# EMMC.net
KiCad netlist of a schematic drawn in Altium Designer
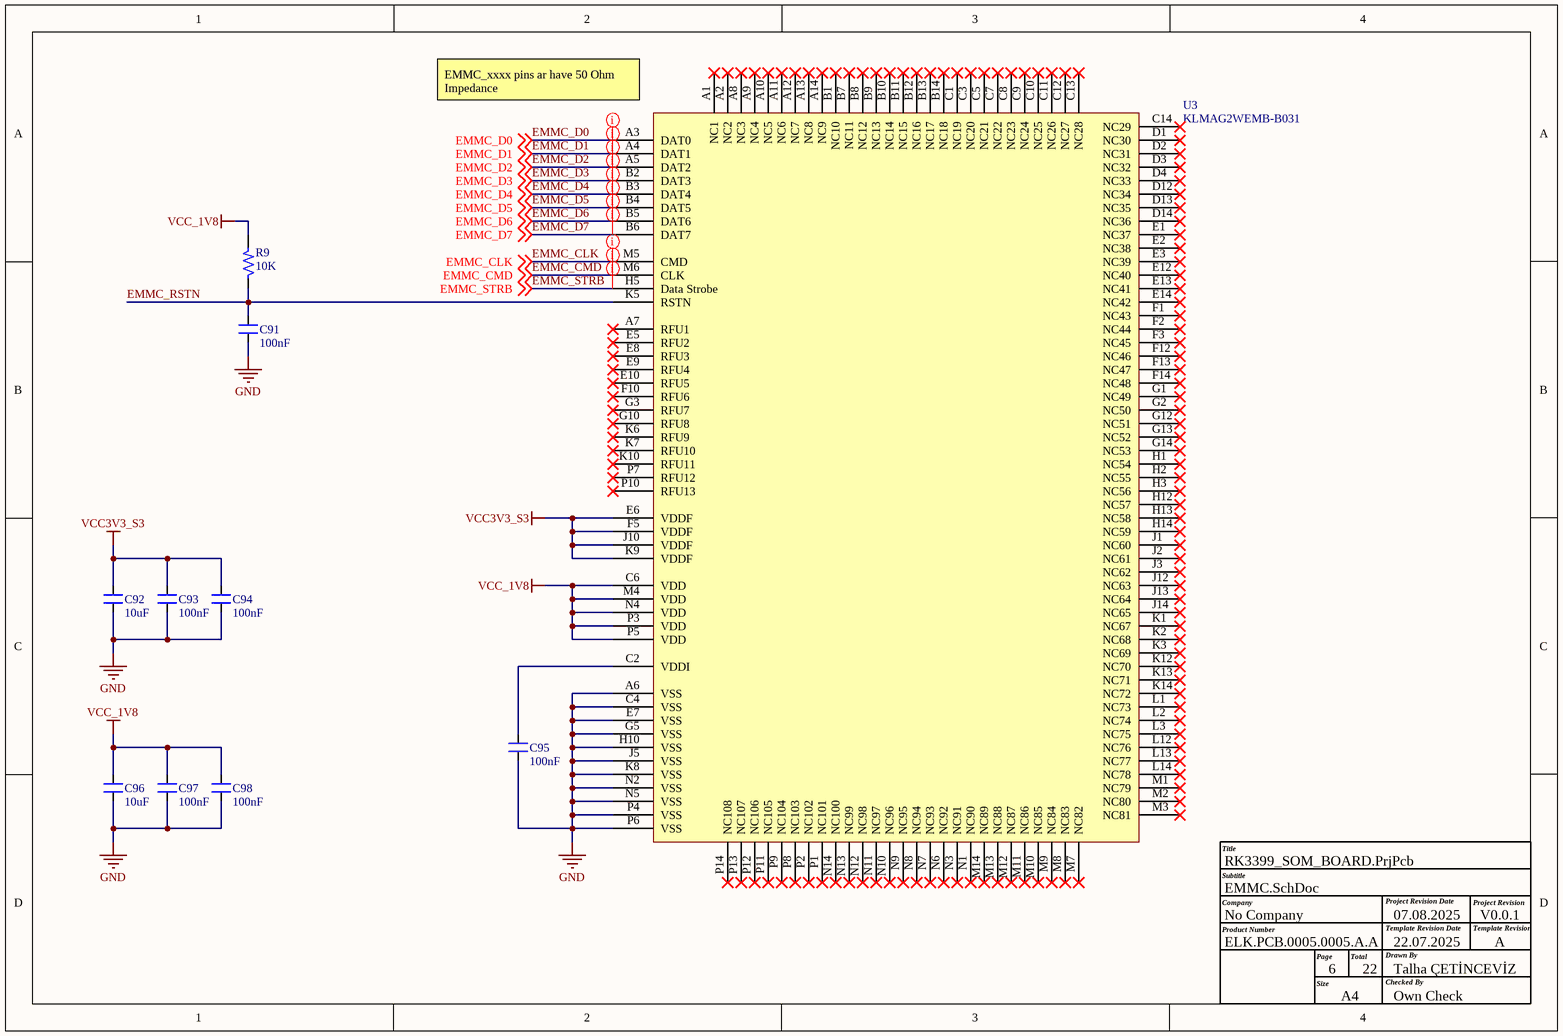
[diagram p0: EMMC.SchDoc]

(export (version "E")
  (design (tool "Eeschema 10.0.6"))
  (components
    (comp (ref "C91")
      (value "100nF")
      (footprint "CAP_0201")
      (description "0.1µF ±10% 25V Ceramic Capacitor X5R 0201 (0603 Metric)")
      (fields
        (field (name "MANUFACTURER") "TDK Corporation")
        (field (name "MANUFACTURER PART NUMBER") "C0603X5R1E104K030BB")
      )
      (libsource (lib "EsteemPCB_SOM_Course_intlib") (part "CAP_100nF-25V-10%-0201"))
    )
    (comp (ref "C92")
      (value "10uF")
      (footprint "CAP_0603")
      (description "10µF ±10% 10V Ceramic Capacitor X5R 0603 (1608 Metric)")
      (fields
        (field (name "MANUFACTURER PART NUMBER") "GRM188R61A106KE69J")
        (field (name "MANUFACTURER") "Murata Electronics")
      )
      (libsource (lib "EsteemPCB_SOM_Course_intlib") (part "CAP_10uF-10V-10%-0603"))
    )
    (comp (ref "C93")
      (value "100nF")
      (footprint "CAP_0201")
      (description "0.1µF ±10% 25V Ceramic Capacitor X5R 0201 (0603 Metric)")
      (fields
        (field (name "MANUFACTURER") "TDK Corporation")
        (field (name "MANUFACTURER PART NUMBER") "C0603X5R1E104K030BB")
      )
      (libsource (lib "EsteemPCB_SOM_Course_intlib") (part "CAP_100nF-25V-10%-0201"))
    )
    (comp (ref "C94")
      (value "100nF")
      (footprint "CAP_0201")
      (description "0.1µF ±10% 25V Ceramic Capacitor X5R 0201 (0603 Metric)")
      (fields
        (field (name "MANUFACTURER") "TDK Corporation")
        (field (name "MANUFACTURER PART NUMBER") "C0603X5R1E104K030BB")
      )
      (libsource (lib "EsteemPCB_SOM_Course_intlib") (part "CAP_100nF-25V-10%-0201"))
    )
    (comp (ref "C95")
      (value "100nF")
      (footprint "CAP_0201")
      (description "0.1µF ±10% 25V Ceramic Capacitor X5R 0201 (0603 Metric)")
      (fields
        (field (name "MANUFACTURER") "TDK Corporation")
        (field (name "MANUFACTURER PART NUMBER") "C0603X5R1E104K030BB")
      )
      (libsource (lib "EsteemPCB_SOM_Course_intlib") (part "CAP_100nF-25V-10%-0201"))
    )
    (comp (ref "C96")
      (value "10uF")
      (footprint "CAP_0603")
      (description "10µF ±10% 10V Ceramic Capacitor X5R 0603 (1608 Metric)")
      (fields
        (field (name "MANUFACTURER PART NUMBER") "GRM188R61A106KE69J")
        (field (name "MANUFACTURER") "Murata Electronics")
      )
      (libsource (lib "EsteemPCB_SOM_Course_intlib") (part "CAP_10uF-10V-10%-0603"))
    )
    (comp (ref "C97")
      (value "100nF")
      (footprint "CAP_0201")
      (description "0.1µF ±10% 25V Ceramic Capacitor X5R 0201 (0603 Metric)")
      (fields
        (field (name "MANUFACTURER") "TDK Corporation")
        (field (name "MANUFACTURER PART NUMBER") "C0603X5R1E104K030BB")
      )
      (libsource (lib "EsteemPCB_SOM_Course_intlib") (part "CAP_100nF-25V-10%-0201"))
    )
    (comp (ref "C98")
      (value "100nF")
      (footprint "CAP_0201")
      (description "0.1µF ±10% 25V Ceramic Capacitor X5R 0201 (0603 Metric)")
      (fields
        (field (name "MANUFACTURER") "TDK Corporation")
        (field (name "MANUFACTURER PART NUMBER") "C0603X5R1E104K030BB")
      )
      (libsource (lib "EsteemPCB_SOM_Course_intlib") (part "CAP_100nF-25V-10%-0201"))
    )
    (comp (ref "R9")
      (value "10K")
      (footprint "RES_0201")
      (description "10 kOhms ±1% 0.05W, 1/20W Chip Resistor 0201 (0603 Metric) Thick Film")
      (fields
        (field (name "MANUFACTURER") "Stackpole Electronics Inc")
        (field (name "MANUFACTURER PART NUMBER") "RMCF0201FT10K0")
      )
      (libsource (lib "EsteemPCB_SOM_Course_intlib") (part "RES_10K-0.05W-1%-0201"))
    )
    (comp (ref "U3")
      (value "KLMAG2WEMB-B031")
      (footprint "BGA153C50P14X14_1150X1300X70")
      (description "16GB NAND Flash Memory")
      (fields (field (name "MANUFACTURER") "Samsung Electronics"))
      (libsource (lib "EsteemPCB_SOM_Course_intlib") (part "IC_KLMAG2WEMB-B031"))
    )
  )
  (nets
    (net (code "1") (name "/EMMC_RSTN") (class "Default")
      (node (ref "C91") (pin "2") (pinfunction "2_2") (pintype "passive"))
      (node (ref "R9") (pin "1") (pinfunction "1_1") (pintype "passive"))
      (node (ref "U3") (pin "K5") (pinfunction "RSTN_K5") (pintype "passive"))
    )
    (net (code "2") (name "EMMC_CLK") (class "Default")
      (node (ref "U3") (pin "M5") (pinfunction "CMD_M5") (pintype "passive"))
    )
    (net (code "3") (name "EMMC_CMD") (class "Default")
      (node (ref "U3") (pin "M6") (pinfunction "CLK_M6") (pintype "passive"))
    )
    (net (code "4") (name "EMMC_D0") (class "Default")
      (node (ref "U3") (pin "A3") (pinfunction "DAT0_A3") (pintype "passive"))
    )
    (net (code "5") (name "EMMC_D1") (class "Default")
      (node (ref "U3") (pin "A4") (pinfunction "DAT1_A4") (pintype "passive"))
    )
    (net (code "6") (name "EMMC_D2") (class "Default")
      (node (ref "U3") (pin "A5") (pinfunction "DAT2_A5") (pintype "passive"))
    )
    (net (code "7") (name "EMMC_D3") (class "Default")
      (node (ref "U3") (pin "B2") (pinfunction "DAT3_B2") (pintype "passive"))
    )
    (net (code "8") (name "EMMC_D4") (class "Default")
      (node (ref "U3") (pin "B3") (pinfunction "DAT4_B3") (pintype "passive"))
    )
    (net (code "9") (name "EMMC_D5") (class "Default")
      (node (ref "U3") (pin "B4") (pinfunction "DAT5_B4") (pintype "passive"))
    )
    (net (code "10") (name "EMMC_D6") (class "Default")
      (node (ref "U3") (pin "B5") (pinfunction "DAT6_B5") (pintype "passive"))
    )
    (net (code "11") (name "EMMC_D7") (class "Default")
      (node (ref "U3") (pin "B6") (pinfunction "DAT7_B6") (pintype "passive"))
    )
    (net (code "12") (name "EMMC_STRB") (class "Default")
      (node (ref "U3") (pin "H5") (pinfunction "Data_Strobe_H5") (pintype "passive"))
    )
    (net (code "13") (name "GND") (class "Default")
      (node (ref "C91") (pin "1") (pinfunction "1_1") (pintype "passive"))
      (node (ref "C92") (pin "1") (pinfunction "1_1") (pintype "passive"))
      (node (ref "C93") (pin "1") (pinfunction "1_1") (pintype "passive"))
      (node (ref "C94") (pin "1") (pinfunction "1_1") (pintype "passive"))
      (node (ref "C95") (pin "2") (pinfunction "2_2") (pintype "passive"))
      (node (ref "C96") (pin "1") (pinfunction "1_1") (pintype "passive"))
      (node (ref "C97") (pin "1") (pinfunction "1_1") (pintype "passive"))
      (node (ref "C98") (pin "1") (pinfunction "1_1") (pintype "passive"))
      (node (ref "U3") (pin "A6") (pinfunction "VSS_A6") (pintype "passive"))
      (node (ref "U3") (pin "C4") (pinfunction "VSS_C4") (pintype "passive"))
      (node (ref "U3") (pin "E7") (pinfunction "VSS_E7") (pintype "passive"))
      (node (ref "U3") (pin "G5") (pinfunction "VSS_G5") (pintype "passive"))
      (node (ref "U3") (pin "H10") (pinfunction "VSS_H10") (pintype "passive"))
      (node (ref "U3") (pin "J5") (pinfunction "VSS_J5") (pintype "passive"))
      (node (ref "U3") (pin "K8") (pinfunction "VSS_K8") (pintype "passive"))
      (node (ref "U3") (pin "N2") (pinfunction "VSS_N2") (pintype "passive"))
      (node (ref "U3") (pin "N5") (pinfunction "VSS_N5") (pintype "passive"))
      (node (ref "U3") (pin "P4") (pinfunction "VSS_P4") (pintype "passive"))
      (node (ref "U3") (pin "P6") (pinfunction "VSS_P6") (pintype "passive"))
    )
    (net (code "14") (name "Net-(U3-VDDI)") (class "Default")
      (node (ref "C95") (pin "1") (pinfunction "1_1") (pintype "passive"))
      (node (ref "U3") (pin "C2") (pinfunction "VDDI_C2") (pintype "passive"))
    )
    (net (code "15") (name "VCC3V3_S3") (class "Default")
      (node (ref "C92") (pin "2") (pinfunction "2_2") (pintype "passive"))
      (node (ref "C93") (pin "2") (pinfunction "2_2") (pintype "passive"))
      (node (ref "C94") (pin "2") (pinfunction "2_2") (pintype "passive"))
      (node (ref "U3") (pin "E6") (pinfunction "VDDF_E6") (pintype "passive"))
      (node (ref "U3") (pin "F5") (pinfunction "VDDF_F5") (pintype "passive"))
      (node (ref "U3") (pin "J10") (pinfunction "VDDF_J10") (pintype "passive"))
      (node (ref "U3") (pin "K9") (pinfunction "VDDF_K9") (pintype "passive"))
    )
    (net (code "16") (name "VCC_1V8") (class "Default")
      (node (ref "C96") (pin "2") (pinfunction "2_2") (pintype "passive"))
      (node (ref "C97") (pin "2") (pinfunction "2_2") (pintype "passive"))
      (node (ref "C98") (pin "2") (pinfunction "2_2") (pintype "passive"))
      (node (ref "R9") (pin "2") (pinfunction "2_2") (pintype "passive"))
      (node (ref "U3") (pin "C6") (pinfunction "VDD_C6") (pintype "passive"))
      (node (ref "U3") (pin "M4") (pinfunction "VDD_M4") (pintype "passive"))
      (node (ref "U3") (pin "N4") (pinfunction "VDD_N4") (pintype "passive"))
      (node (ref "U3") (pin "P3") (pinfunction "VDD_P3") (pintype "passive"))
      (node (ref "U3") (pin "P5") (pinfunction "VDD_P5") (pintype "passive"))
    )
    (net (code "17") (name "unconnected-(U3-NC1-PadA1)") (class "Default")
      (node (ref "U3") (pin "A1") (pinfunction "NC1_A1") (pintype "passive+no_connect"))
    )
    (net (code "18") (name "unconnected-(U3-NC2-PadA2)") (class "Default")
      (node (ref "U3") (pin "A2") (pinfunction "NC2_A2") (pintype "passive+no_connect"))
    )
    (net (code "19") (name "unconnected-(U3-NC3-PadA8)") (class "Default")
      (node (ref "U3") (pin "A8") (pinfunction "NC3_A8") (pintype "passive+no_connect"))
    )
    (net (code "20") (name "unconnected-(U3-NC4-PadA9)") (class "Default")
      (node (ref "U3") (pin "A9") (pinfunction "NC4_A9") (pintype "passive+no_connect"))
    )
    (net (code "21") (name "unconnected-(U3-NC5-PadA10)") (class "Default")
      (node (ref "U3") (pin "A10") (pinfunction "NC5_A10") (pintype "passive+no_connect"))
    )
    (net (code "22") (name "unconnected-(U3-NC6-PadA11)") (class "Default")
      (node (ref "U3") (pin "A11") (pinfunction "NC6_A11") (pintype "passive+no_connect"))
    )
    (net (code "23") (name "unconnected-(U3-NC7-PadA12)") (class "Default")
      (node (ref "U3") (pin "A12") (pinfunction "NC7_A12") (pintype "passive+no_connect"))
    )
    (net (code "24") (name "unconnected-(U3-NC8-PadA13)") (class "Default")
      (node (ref "U3") (pin "A13") (pinfunction "NC8_A13") (pintype "passive+no_connect"))
    )
    (net (code "25") (name "unconnected-(U3-NC9-PadA14)") (class "Default")
      (node (ref "U3") (pin "A14") (pinfunction "NC9_A14") (pintype "passive+no_connect"))
    )
    (net (code "26") (name "unconnected-(U3-NC10-PadB1)") (class "Default")
      (node (ref "U3") (pin "B1") (pinfunction "NC10_B1") (pintype "passive+no_connect"))
    )
    (net (code "27") (name "unconnected-(U3-NC11-PadB7)") (class "Default")
      (node (ref "U3") (pin "B7") (pinfunction "NC11_B7") (pintype "passive+no_connect"))
    )
    (net (code "28") (name "unconnected-(U3-NC12-PadB8)") (class "Default")
      (node (ref "U3") (pin "B8") (pinfunction "NC12_B8") (pintype "passive+no_connect"))
    )
    (net (code "29") (name "unconnected-(U3-NC13-PadB9)") (class "Default")
      (node (ref "U3") (pin "B9") (pinfunction "NC13_B9") (pintype "passive+no_connect"))
    )
    (net (code "30") (name "unconnected-(U3-NC14-PadB10)") (class "Default")
      (node (ref "U3") (pin "B10") (pinfunction "NC14_B10") (pintype "passive+no_connect"))
    )
    (net (code "31") (name "unconnected-(U3-NC15-PadB11)") (class "Default")
      (node (ref "U3") (pin "B11") (pinfunction "NC15_B11") (pintype "passive+no_connect"))
    )
    (net (code "32") (name "unconnected-(U3-NC16-PadB12)") (class "Default")
      (node (ref "U3") (pin "B12") (pinfunction "NC16_B12") (pintype "passive+no_connect"))
    )
    (net (code "33") (name "unconnected-(U3-NC17-PadB13)") (class "Default")
      (node (ref "U3") (pin "B13") (pinfunction "NC17_B13") (pintype "passive+no_connect"))
    )
    (net (code "34") (name "unconnected-(U3-NC18-PadB14)") (class "Default")
      (node (ref "U3") (pin "B14") (pinfunction "NC18_B14") (pintype "passive+no_connect"))
    )
    (net (code "35") (name "unconnected-(U3-NC19-PadC1)") (class "Default")
      (node (ref "U3") (pin "C1") (pinfunction "NC19_C1") (pintype "passive+no_connect"))
    )
    (net (code "36") (name "unconnected-(U3-NC20-PadC3)") (class "Default")
      (node (ref "U3") (pin "C3") (pinfunction "NC20_C3") (pintype "passive+no_connect"))
    )
    (net (code "37") (name "unconnected-(U3-NC21-PadC5)") (class "Default")
      (node (ref "U3") (pin "C5") (pinfunction "NC21_C5") (pintype "passive+no_connect"))
    )
    (net (code "38") (name "unconnected-(U3-NC22-PadC7)") (class "Default")
      (node (ref "U3") (pin "C7") (pinfunction "NC22_C7") (pintype "passive+no_connect"))
    )
    (net (code "39") (name "unconnected-(U3-NC23-PadC8)") (class "Default")
      (node (ref "U3") (pin "C8") (pinfunction "NC23_C8") (pintype "passive+no_connect"))
    )
    (net (code "40") (name "unconnected-(U3-NC24-PadC9)") (class "Default")
      (node (ref "U3") (pin "C9") (pinfunction "NC24_C9") (pintype "passive+no_connect"))
    )
    (net (code "41") (name "unconnected-(U3-NC25-PadC10)") (class "Default")
      (node (ref "U3") (pin "C10") (pinfunction "NC25_C10") (pintype "passive+no_connect"))
    )
    (net (code "42") (name "unconnected-(U3-NC26-PadC11)") (class "Default")
      (node (ref "U3") (pin "C11") (pinfunction "NC26_C11") (pintype "passive+no_connect"))
    )
    (net (code "43") (name "unconnected-(U3-NC27-PadC12)") (class "Default")
      (node (ref "U3") (pin "C12") (pinfunction "NC27_C12") (pintype "passive+no_connect"))
    )
    (net (code "44") (name "unconnected-(U3-NC28-PadC13)") (class "Default")
      (node (ref "U3") (pin "C13") (pinfunction "NC28_C13") (pintype "passive+no_connect"))
    )
    (net (code "45") (name "unconnected-(U3-NC29-PadC14)") (class "Default")
      (node (ref "U3") (pin "C14") (pinfunction "NC29_C14") (pintype "passive+no_connect"))
    )
    (net (code "46") (name "unconnected-(U3-NC30-PadD1)") (class "Default")
      (node (ref "U3") (pin "D1") (pinfunction "NC30_D1") (pintype "passive+no_connect"))
    )
    (net (code "47") (name "unconnected-(U3-NC31-PadD2)") (class "Default")
      (node (ref "U3") (pin "D2") (pinfunction "NC31_D2") (pintype "passive+no_connect"))
    )
    (net (code "48") (name "unconnected-(U3-NC32-PadD3)") (class "Default")
      (node (ref "U3") (pin "D3") (pinfunction "NC32_D3") (pintype "passive+no_connect"))
    )
    (net (code "49") (name "unconnected-(U3-NC33-PadD4)") (class "Default")
      (node (ref "U3") (pin "D4") (pinfunction "NC33_D4") (pintype "passive+no_connect"))
    )
    (net (code "50") (name "unconnected-(U3-NC34-PadD12)") (class "Default")
      (node (ref "U3") (pin "D12") (pinfunction "NC34_D12") (pintype "passive+no_connect"))
    )
    (net (code "51") (name "unconnected-(U3-NC35-PadD13)") (class "Default")
      (node (ref "U3") (pin "D13") (pinfunction "NC35_D13") (pintype "passive+no_connect"))
    )
    (net (code "52") (name "unconnected-(U3-NC36-PadD14)") (class "Default")
      (node (ref "U3") (pin "D14") (pinfunction "NC36_D14") (pintype "passive+no_connect"))
    )
    (net (code "53") (name "unconnected-(U3-NC37-PadE1)") (class "Default")
      (node (ref "U3") (pin "E1") (pinfunction "NC37_E1") (pintype "passive+no_connect"))
    )
    (net (code "54") (name "unconnected-(U3-NC38-PadE2)") (class "Default")
      (node (ref "U3") (pin "E2") (pinfunction "NC38_E2") (pintype "passive+no_connect"))
    )
    (net (code "55") (name "unconnected-(U3-NC39-PadE3)") (class "Default")
      (node (ref "U3") (pin "E3") (pinfunction "NC39_E3") (pintype "passive+no_connect"))
    )
    (net (code "56") (name "unconnected-(U3-NC40-PadE12)") (class "Default")
      (node (ref "U3") (pin "E12") (pinfunction "NC40_E12") (pintype "passive+no_connect"))
    )
    (net (code "57") (name "unconnected-(U3-NC41-PadE13)") (class "Default")
      (node (ref "U3") (pin "E13") (pinfunction "NC41_E13") (pintype "passive+no_connect"))
    )
    (net (code "58") (name "unconnected-(U3-NC42-PadE14)") (class "Default")
      (node (ref "U3") (pin "E14") (pinfunction "NC42_E14") (pintype "passive+no_connect"))
    )
    (net (code "59") (name "unconnected-(U3-NC43-PadF1)") (class "Default")
      (node (ref "U3") (pin "F1") (pinfunction "NC43_F1") (pintype "passive+no_connect"))
    )
    (net (code "60") (name "unconnected-(U3-NC44-PadF2)") (class "Default")
      (node (ref "U3") (pin "F2") (pinfunction "NC44_F2") (pintype "passive+no_connect"))
    )
    (net (code "61") (name "unconnected-(U3-NC45-PadF3)") (class "Default")
      (node (ref "U3") (pin "F3") (pinfunction "NC45_F3") (pintype "passive+no_connect"))
    )
    (net (code "62") (name "unconnected-(U3-NC46-PadF12)") (class "Default")
      (node (ref "U3") (pin "F12") (pinfunction "NC46_F12") (pintype "passive+no_connect"))
    )
    (net (code "63") (name "unconnected-(U3-NC47-PadF13)") (class "Default")
      (node (ref "U3") (pin "F13") (pinfunction "NC47_F13") (pintype "passive+no_connect"))
    )
    (net (code "64") (name "unconnected-(U3-NC48-PadF14)") (class "Default")
      (node (ref "U3") (pin "F14") (pinfunction "NC48_F14") (pintype "passive+no_connect"))
    )
    (net (code "65") (name "unconnected-(U3-NC49-PadG1)") (class "Default")
      (node (ref "U3") (pin "G1") (pinfunction "NC49_G1") (pintype "passive+no_connect"))
    )
    (net (code "66") (name "unconnected-(U3-NC50-PadG2)") (class "Default")
      (node (ref "U3") (pin "G2") (pinfunction "NC50_G2") (pintype "passive+no_connect"))
    )
    (net (code "67") (name "unconnected-(U3-NC51-PadG12)") (class "Default")
      (node (ref "U3") (pin "G12") (pinfunction "NC51_G12") (pintype "passive+no_connect"))
    )
    (net (code "68") (name "unconnected-(U3-NC52-PadG13)") (class "Default")
      (node (ref "U3") (pin "G13") (pinfunction "NC52_G13") (pintype "passive+no_connect"))
    )
    (net (code "69") (name "unconnected-(U3-NC53-PadG14)") (class "Default")
      (node (ref "U3") (pin "G14") (pinfunction "NC53_G14") (pintype "passive+no_connect"))
    )
    (net (code "70") (name "unconnected-(U3-NC54-PadH1)") (class "Default")
      (node (ref "U3") (pin "H1") (pinfunction "NC54_H1") (pintype "passive+no_connect"))
    )
    (net (code "71") (name "unconnected-(U3-NC55-PadH2)") (class "Default")
      (node (ref "U3") (pin "H2") (pinfunction "NC55_H2") (pintype "passive+no_connect"))
    )
    (net (code "72") (name "unconnected-(U3-NC56-PadH3)") (class "Default")
      (node (ref "U3") (pin "H3") (pinfunction "NC56_H3") (pintype "passive+no_connect"))
    )
    (net (code "73") (name "unconnected-(U3-NC57-PadH12)") (class "Default")
      (node (ref "U3") (pin "H12") (pinfunction "NC57_H12") (pintype "passive+no_connect"))
    )
    (net (code "74") (name "unconnected-(U3-NC58-PadH13)") (class "Default")
      (node (ref "U3") (pin "H13") (pinfunction "NC58_H13") (pintype "passive+no_connect"))
    )
    (net (code "75") (name "unconnected-(U3-NC59-PadH14)") (class "Default")
      (node (ref "U3") (pin "H14") (pinfunction "NC59_H14") (pintype "passive+no_connect"))
    )
    (net (code "76") (name "unconnected-(U3-NC60-PadJ1)") (class "Default")
      (node (ref "U3") (pin "J1") (pinfunction "NC60_J1") (pintype "passive+no_connect"))
    )
    (net (code "77") (name "unconnected-(U3-NC61-PadJ2)") (class "Default")
      (node (ref "U3") (pin "J2") (pinfunction "NC61_J2") (pintype "passive+no_connect"))
    )
    (net (code "78") (name "unconnected-(U3-NC62-PadJ3)") (class "Default")
      (node (ref "U3") (pin "J3") (pinfunction "NC62_J3") (pintype "passive+no_connect"))
    )
    (net (code "79") (name "unconnected-(U3-NC63-PadJ12)") (class "Default")
      (node (ref "U3") (pin "J12") (pinfunction "NC63_J12") (pintype "passive+no_connect"))
    )
    (net (code "80") (name "unconnected-(U3-NC64-PadJ13)") (class "Default")
      (node (ref "U3") (pin "J13") (pinfunction "NC64_J13") (pintype "passive+no_connect"))
    )
    (net (code "81") (name "unconnected-(U3-NC65-PadJ14)") (class "Default")
      (node (ref "U3") (pin "J14") (pinfunction "NC65_J14") (pintype "passive+no_connect"))
    )
    (net (code "82") (name "unconnected-(U3-NC67-PadK1)") (class "Default")
      (node (ref "U3") (pin "K1") (pinfunction "NC67_K1") (pintype "passive+no_connect"))
    )
    (net (code "83") (name "unconnected-(U3-NC68-PadK2)") (class "Default")
      (node (ref "U3") (pin "K2") (pinfunction "NC68_K2") (pintype "passive+no_connect"))
    )
    (net (code "84") (name "unconnected-(U3-NC69-PadK3)") (class "Default")
      (node (ref "U3") (pin "K3") (pinfunction "NC69_K3") (pintype "passive+no_connect"))
    )
    (net (code "85") (name "unconnected-(U3-NC70-PadK12)") (class "Default")
      (node (ref "U3") (pin "K12") (pinfunction "NC70_K12") (pintype "passive+no_connect"))
    )
    (net (code "86") (name "unconnected-(U3-NC71-PadK13)") (class "Default")
      (node (ref "U3") (pin "K13") (pinfunction "NC71_K13") (pintype "passive+no_connect"))
    )
    (net (code "87") (name "unconnected-(U3-NC72-PadK14)") (class "Default")
      (node (ref "U3") (pin "K14") (pinfunction "NC72_K14") (pintype "passive+no_connect"))
    )
    (net (code "88") (name "unconnected-(U3-NC73-PadL1)") (class "Default")
      (node (ref "U3") (pin "L1") (pinfunction "NC73_L1") (pintype "passive+no_connect"))
    )
    (net (code "89") (name "unconnected-(U3-NC74-PadL2)") (class "Default")
      (node (ref "U3") (pin "L2") (pinfunction "NC74_L2") (pintype "passive+no_connect"))
    )
    (net (code "90") (name "unconnected-(U3-NC75-PadL3)") (class "Default")
      (node (ref "U3") (pin "L3") (pinfunction "NC75_L3") (pintype "passive+no_connect"))
    )
    (net (code "91") (name "unconnected-(U3-NC76-PadL12)") (class "Default")
      (node (ref "U3") (pin "L12") (pinfunction "NC76_L12") (pintype "passive+no_connect"))
    )
    (net (code "92") (name "unconnected-(U3-NC77-PadL13)") (class "Default")
      (node (ref "U3") (pin "L13") (pinfunction "NC77_L13") (pintype "passive+no_connect"))
    )
    (net (code "93") (name "unconnected-(U3-NC78-PadL14)") (class "Default")
      (node (ref "U3") (pin "L14") (pinfunction "NC78_L14") (pintype "passive+no_connect"))
    )
    (net (code "94") (name "unconnected-(U3-NC79-PadM1)") (class "Default")
      (node (ref "U3") (pin "M1") (pinfunction "NC79_M1") (pintype "passive+no_connect"))
    )
    (net (code "95") (name "unconnected-(U3-NC80-PadM2)") (class "Default")
      (node (ref "U3") (pin "M2") (pinfunction "NC80_M2") (pintype "passive+no_connect"))
    )
    (net (code "96") (name "unconnected-(U3-NC81-PadM3)") (class "Default")
      (node (ref "U3") (pin "M3") (pinfunction "NC81_M3") (pintype "passive+no_connect"))
    )
    (net (code "97") (name "unconnected-(U3-NC82-PadM7)") (class "Default")
      (node (ref "U3") (pin "M7") (pinfunction "NC82_M7") (pintype "passive+no_connect"))
    )
    (net (code "98") (name "unconnected-(U3-NC83-PadM8)") (class "Default")
      (node (ref "U3") (pin "M8") (pinfunction "NC83_M8") (pintype "passive+no_connect"))
    )
    (net (code "99") (name "unconnected-(U3-NC84-PadM9)") (class "Default")
      (node (ref "U3") (pin "M9") (pinfunction "NC84_M9") (pintype "passive+no_connect"))
    )
    (net (code "100") (name "unconnected-(U3-NC85-PadM10)") (class "Default")
      (node (ref "U3") (pin "M10") (pinfunction "NC85_M10") (pintype "passive+no_connect"))
    )
    (net (code "101") (name "unconnected-(U3-NC86-PadM11)") (class "Default")
      (node (ref "U3") (pin "M11") (pinfunction "NC86_M11") (pintype "passive+no_connect"))
    )
    (net (code "102") (name "unconnected-(U3-NC87-PadM12)") (class "Default")
      (node (ref "U3") (pin "M12") (pinfunction "NC87_M12") (pintype "passive+no_connect"))
    )
    (net (code "103") (name "unconnected-(U3-NC88-PadM13)") (class "Default")
      (node (ref "U3") (pin "M13") (pinfunction "NC88_M13") (pintype "passive+no_connect"))
    )
    (net (code "104") (name "unconnected-(U3-NC89-PadM14)") (class "Default")
      (node (ref "U3") (pin "M14") (pinfunction "NC89_M14") (pintype "passive+no_connect"))
    )
    (net (code "105") (name "unconnected-(U3-NC90-PadN1)") (class "Default")
      (node (ref "U3") (pin "N1") (pinfunction "NC90_N1") (pintype "passive+no_connect"))
    )
    (net (code "106") (name "unconnected-(U3-NC91-PadN3)") (class "Default")
      (node (ref "U3") (pin "N3") (pinfunction "NC91_N3") (pintype "passive+no_connect"))
    )
    (net (code "107") (name "unconnected-(U3-NC92-PadN6)") (class "Default")
      (node (ref "U3") (pin "N6") (pinfunction "NC92_N6") (pintype "passive+no_connect"))
    )
    (net (code "108") (name "unconnected-(U3-NC93-PadN7)") (class "Default")
      (node (ref "U3") (pin "N7") (pinfunction "NC93_N7") (pintype "passive+no_connect"))
    )
    (net (code "109") (name "unconnected-(U3-NC94-PadN8)") (class "Default")
      (node (ref "U3") (pin "N8") (pinfunction "NC94_N8") (pintype "passive+no_connect"))
    )
    (net (code "110") (name "unconnected-(U3-NC95-PadN9)") (class "Default")
      (node (ref "U3") (pin "N9") (pinfunction "NC95_N9") (pintype "passive+no_connect"))
    )
    (net (code "111") (name "unconnected-(U3-NC96-PadN10)") (class "Default")
      (node (ref "U3") (pin "N10") (pinfunction "NC96_N10") (pintype "passive+no_connect"))
    )
    (net (code "112") (name "unconnected-(U3-NC97-PadN11)") (class "Default")
      (node (ref "U3") (pin "N11") (pinfunction "NC97_N11") (pintype "passive+no_connect"))
    )
    (net (code "113") (name "unconnected-(U3-NC98-PadN12)") (class "Default")
      (node (ref "U3") (pin "N12") (pinfunction "NC98_N12") (pintype "passive+no_connect"))
    )
    (net (code "114") (name "unconnected-(U3-NC99-PadN13)") (class "Default")
      (node (ref "U3") (pin "N13") (pinfunction "NC99_N13") (pintype "passive+no_connect"))
    )
    (net (code "115") (name "unconnected-(U3-NC100-PadN14)") (class "Default")
      (node (ref "U3") (pin "N14") (pinfunction "NC100_N14") (pintype "passive+no_connect"))
    )
    (net (code "116") (name "unconnected-(U3-NC101-PadP1)") (class "Default")
      (node (ref "U3") (pin "P1") (pinfunction "NC101_P1") (pintype "passive+no_connect"))
    )
    (net (code "117") (name "unconnected-(U3-NC102-PadP2)") (class "Default")
      (node (ref "U3") (pin "P2") (pinfunction "NC102_P2") (pintype "passive+no_connect"))
    )
    (net (code "118") (name "unconnected-(U3-NC103-PadP8)") (class "Default")
      (node (ref "U3") (pin "P8") (pinfunction "NC103_P8") (pintype "passive+no_connect"))
    )
    (net (code "119") (name "unconnected-(U3-NC104-PadP9)") (class "Default")
      (node (ref "U3") (pin "P9") (pinfunction "NC104_P9") (pintype "passive+no_connect"))
    )
    (net (code "120") (name "unconnected-(U3-NC105-PadP11)") (class "Default")
      (node (ref "U3") (pin "P11") (pinfunction "NC105_P11") (pintype "passive+no_connect"))
    )
    (net (code "121") (name "unconnected-(U3-NC106-PadP12)") (class "Default")
      (node (ref "U3") (pin "P12") (pinfunction "NC106_P12") (pintype "passive+no_connect"))
    )
    (net (code "122") (name "unconnected-(U3-NC107-PadP13)") (class "Default")
      (node (ref "U3") (pin "P13") (pinfunction "NC107_P13") (pintype "passive+no_connect"))
    )
    (net (code "123") (name "unconnected-(U3-NC108-PadP14)") (class "Default")
      (node (ref "U3") (pin "P14") (pinfunction "NC108_P14") (pintype "passive+no_connect"))
    )
    (net (code "124") (name "unconnected-(U3-RFU1-PadA7)") (class "Default")
      (node (ref "U3") (pin "A7") (pinfunction "RFU1_A7") (pintype "passive+no_connect"))
    )
    (net (code "125") (name "unconnected-(U3-RFU2-PadE5)") (class "Default")
      (node (ref "U3") (pin "E5") (pinfunction "RFU2_E5") (pintype "passive+no_connect"))
    )
    (net (code "126") (name "unconnected-(U3-RFU3-PadE8)") (class "Default")
      (node (ref "U3") (pin "E8") (pinfunction "RFU3_E8") (pintype "passive+no_connect"))
    )
    (net (code "127") (name "unconnected-(U3-RFU4-PadE9)") (class "Default")
      (node (ref "U3") (pin "E9") (pinfunction "RFU4_E9") (pintype "passive+no_connect"))
    )
    (net (code "128") (name "unconnected-(U3-RFU5-PadE10)") (class "Default")
      (node (ref "U3") (pin "E10") (pinfunction "RFU5_E10") (pintype "passive+no_connect"))
    )
    (net (code "129") (name "unconnected-(U3-RFU6-PadF10)") (class "Default")
      (node (ref "U3") (pin "F10") (pinfunction "RFU6_F10") (pintype "passive+no_connect"))
    )
    (net (code "130") (name "unconnected-(U3-RFU7-PadG3)") (class "Default")
      (node (ref "U3") (pin "G3") (pinfunction "RFU7_G3") (pintype "passive+no_connect"))
    )
    (net (code "131") (name "unconnected-(U3-RFU8-PadG10)") (class "Default")
      (node (ref "U3") (pin "G10") (pinfunction "RFU8_G10") (pintype "passive+no_connect"))
    )
    (net (code "132") (name "unconnected-(U3-RFU9-PadK6)") (class "Default")
      (node (ref "U3") (pin "K6") (pinfunction "RFU9_K6") (pintype "passive+no_connect"))
    )
    (net (code "133") (name "unconnected-(U3-RFU10-PadK7)") (class "Default")
      (node (ref "U3") (pin "K7") (pinfunction "RFU10_K7") (pintype "passive+no_connect"))
    )
    (net (code "134") (name "unconnected-(U3-RFU11-PadK10)") (class "Default")
      (node (ref "U3") (pin "K10") (pinfunction "RFU11_K10") (pintype "passive+no_connect"))
    )
    (net (code "135") (name "unconnected-(U3-RFU12-PadP7)") (class "Default")
      (node (ref "U3") (pin "P7") (pinfunction "RFU12_P7") (pintype "passive+no_connect"))
    )
    (net (code "136") (name "unconnected-(U3-RFU13-PadP10)") (class "Default")
      (node (ref "U3") (pin "P10") (pinfunction "RFU13_P10") (pintype "passive+no_connect"))
    )
  )
)
